# RFM69Pi_V5.net
KiCad netlist of a schematic drawn in EAGLE
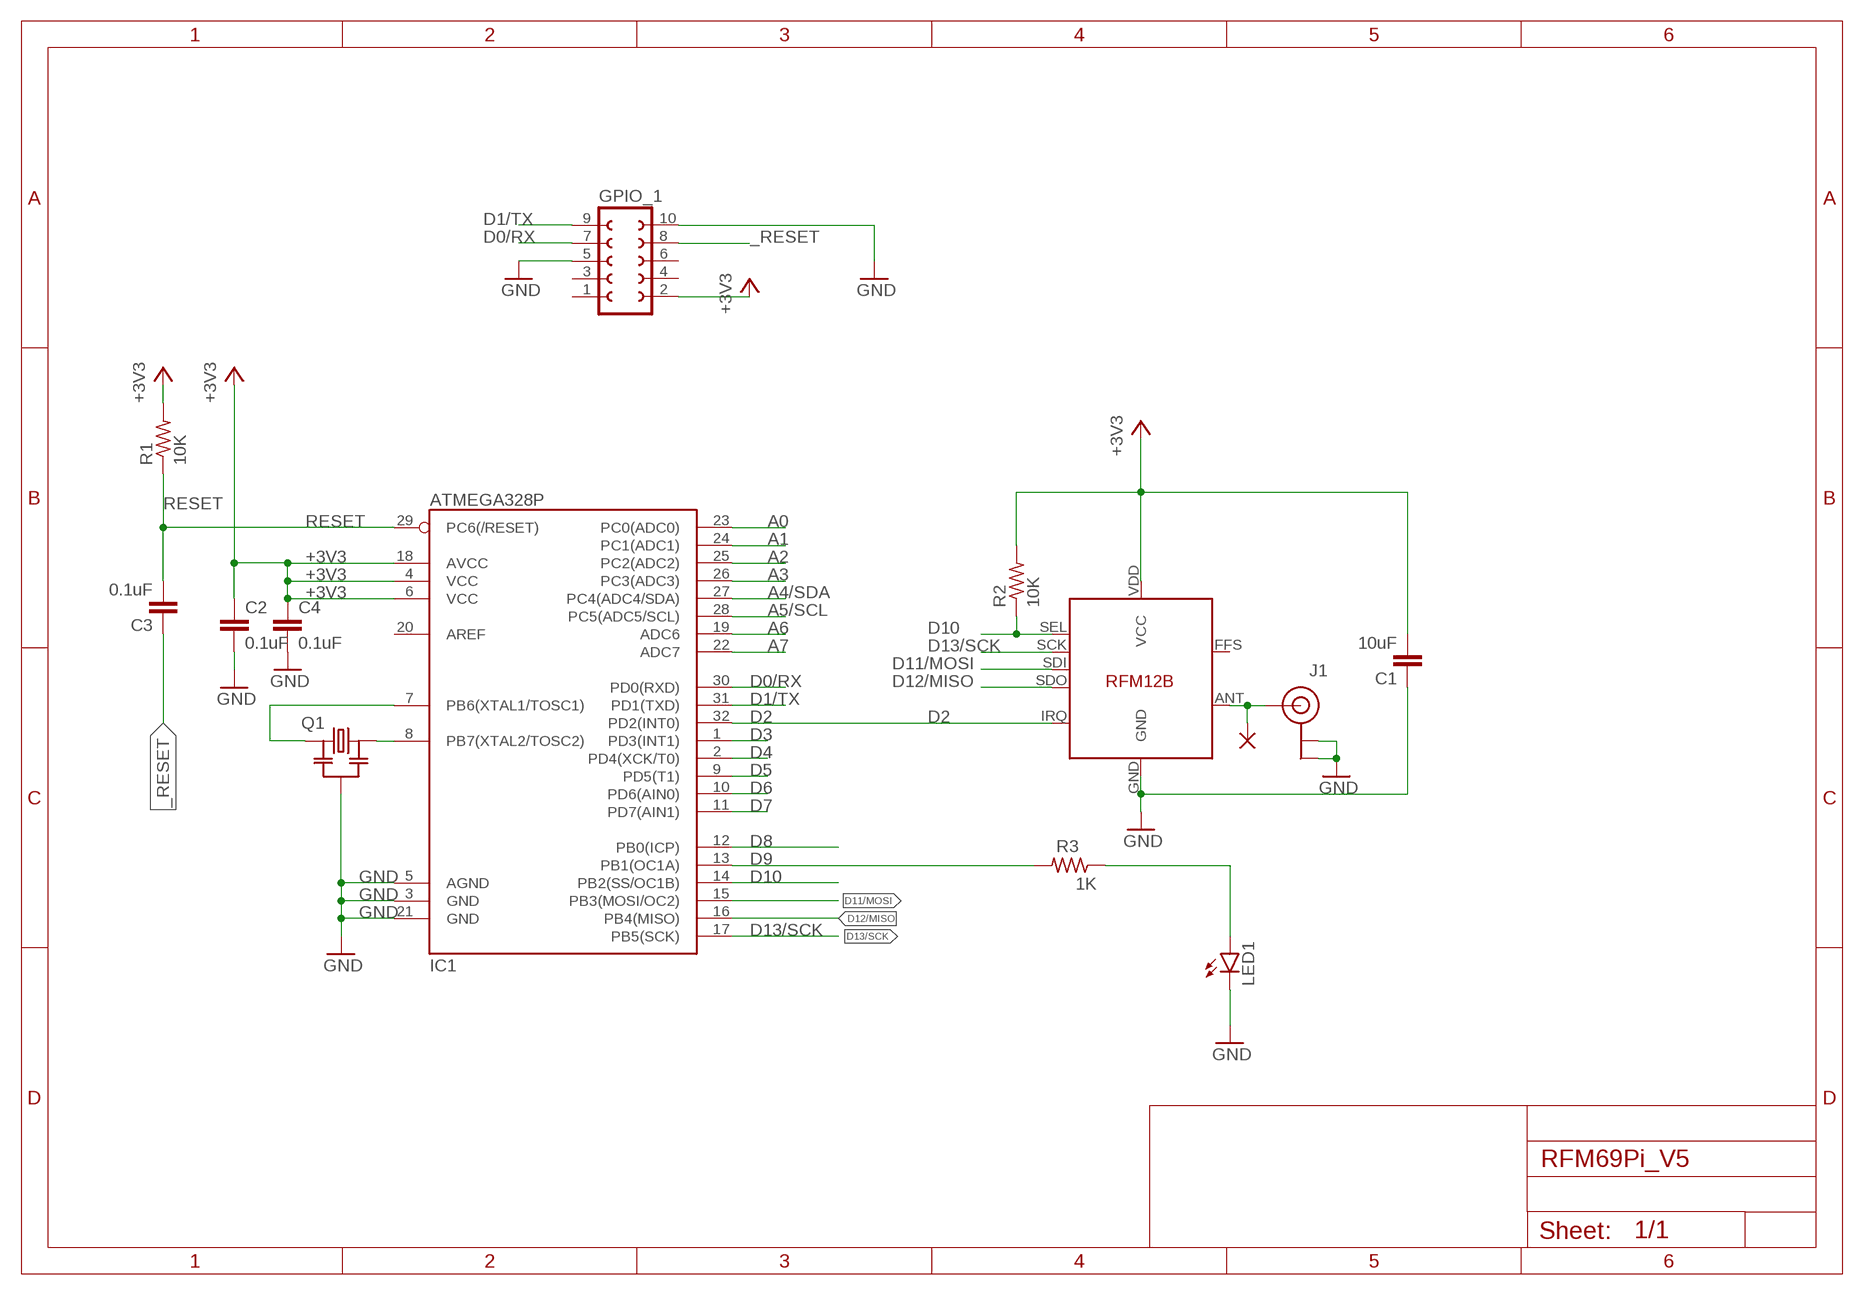
[diagram p0: schematic, sheet 1]

(export (version "E")
  (design (tool "Eeschema 10.0.6"))
  (components
    (comp (ref "C1")
      (value "10uF")
      (footprint "eagle-import:C0603")
      (libsource (lib "eagle-import") (part "C-EUC0603"))
    )
    (comp (ref "C2")
      (value "0.1uF")
      (footprint "eagle-import:C0603")
      (libsource (lib "eagle-import") (part "C-EUC0603"))
    )
    (comp (ref "C3")
      (value "0.1uF")
      (footprint "eagle-import:C0603")
      (libsource (lib "eagle-import") (part "C-EUC0603"))
    )
    (comp (ref "C4")
      (value "0.1uF")
      (footprint "eagle-import:C0603")
      (libsource (lib "eagle-import") (part "resistor_348_C-EUC0603"))
    )
    (comp (ref "GPIO_1")
      (value "CON-LSTA_FE05-2")
      (footprint "eagle-import:CON-LSTA_FE05-2")
      (libsource (lib "eagle-import") (part "CON-LSTA_FE05-2"))
    )
    (comp (ref "IC1")
      (value "ATMEGA328P")
      (footprint "eagle-import:TQFP32-08")
      (libsource (lib "eagle-import") (part "ATMEGA168"))
    )
    (comp (ref "J1")
      (value "U.FL")
      (footprint "eagle-import:U.FL")
      (libsource (lib "eagle-import") (part "U.FL"))
    )
    (comp (ref "LED1")
      (value "LEDSML0603")
      (footprint "eagle-import:SML0603")
      (libsource (lib "eagle-import") (part "LEDSML0603"))
    )
    (comp (ref "PAD2")
      (value "1,6/0,8")
      (footprint "eagle-import:1,6_0,8")
      (libsource (lib "eagle-import") (part "1,6/0,8"))
    )
    (comp (ref "Q1")
      (value "RESONATOR-MURATACST_CE")
      (footprint "eagle-import:RESONATOR_MURATA2")
      (libsource (lib "eagle-import") (part "RESONATOR-MURATACST_CE"))
    )
    (comp (ref "R1")
      (value "10K")
      (footprint "eagle-import:R0603")
      (libsource (lib "eagle-import") (part "R-US_R0603"))
    )
    (comp (ref "R2")
      (value "10K")
      (footprint "eagle-import:R0603")
      (libsource (lib "eagle-import") (part "R-US_R0603"))
    )
    (comp (ref "R3")
      (value "1K")
      (footprint "eagle-import:R0603")
      (libsource (lib "eagle-import") (part "R-US_R0603"))
    )
    (comp (ref "RFM69CW")
      (value "RFM69CW")
      (footprint "eagle-import:RFM12B")
      (libsource (lib "eagle-import") (part "RFM12B"))
    )
  )
  (nets
    (net (code "1") (name "+3V3") (class "Default")
      (node (ref "C1") (pin "2") (pinfunction "2_2") (pintype "passive"))
      (node (ref "C2") (pin "1") (pinfunction "1_1") (pintype "passive"))
      (node (ref "C4") (pin "1") (pinfunction "1_1") (pintype "passive"))
      (node (ref "GPIO_1") (pin "2") (pinfunction "2_2") (pintype "passive"))
      (node (ref "IC1") (pin "18") (pinfunction "AVCC_18") (pintype "bidirectional"))
      (node (ref "IC1") (pin "4") (pinfunction "VCC_4") (pintype "bidirectional"))
      (node (ref "IC1") (pin "6") (pinfunction "VCC_6") (pintype "bidirectional"))
      (node (ref "R1") (pin "2") (pinfunction "2_2") (pintype "passive"))
      (node (ref "R2") (pin "2") (pinfunction "2_2") (pintype "passive"))
      (node (ref "RFM69CW") (pin "VDD") (pinfunction "VCC_VDD") (pintype "power_in"))
    )
    (net (code "2") (name "/A0") (class "Default")
      (node (ref "IC1") (pin "23") (pinfunction "PC0(ADC0)_23") (pintype "bidirectional"))
    )
    (net (code "3") (name "/A1") (class "Default")
      (node (ref "IC1") (pin "24") (pinfunction "PC1(ADC1)_24") (pintype "bidirectional"))
    )
    (net (code "4") (name "/A2") (class "Default")
      (node (ref "IC1") (pin "25") (pinfunction "PC2(ADC2)_25") (pintype "bidirectional"))
    )
    (net (code "5") (name "/A3") (class "Default")
      (node (ref "IC1") (pin "26") (pinfunction "PC3(ADC3)_26") (pintype "bidirectional"))
    )
    (net (code "6") (name "/A4{slash}SDA") (class "Default")
      (node (ref "IC1") (pin "27") (pinfunction "PC4(ADC4/SDA)_27") (pintype "bidirectional"))
    )
    (net (code "7") (name "/A5{slash}SCL") (class "Default")
      (node (ref "IC1") (pin "28") (pinfunction "PC5(ADC5/SCL)_28") (pintype "bidirectional"))
    )
    (net (code "8") (name "/A6") (class "Default")
      (node (ref "IC1") (pin "19") (pinfunction "ADC6_19") (pintype "bidirectional"))
    )
    (net (code "9") (name "/A7") (class "Default")
      (node (ref "IC1") (pin "22") (pinfunction "ADC7_22") (pintype "bidirectional"))
    )
    (net (code "10") (name "/D0{slash}RX") (class "Default")
      (node (ref "GPIO_1") (pin "7") (pinfunction "7_7") (pintype "passive"))
      (node (ref "IC1") (pin "30") (pinfunction "PD0(RXD)_30") (pintype "bidirectional"))
    )
    (net (code "11") (name "/D1{slash}TX") (class "Default")
      (node (ref "GPIO_1") (pin "9") (pinfunction "9_9") (pintype "passive"))
      (node (ref "IC1") (pin "31") (pinfunction "PD1(TXD)_31") (pintype "bidirectional"))
    )
    (net (code "12") (name "/D2") (class "Default")
      (node (ref "IC1") (pin "32") (pinfunction "PD2(INT0)_32") (pintype "bidirectional"))
      (node (ref "RFM69CW") (pin "IRQ") (pinfunction "IRQ_IRQ") (pintype "open_collector"))
    )
    (net (code "13") (name "/D3") (class "Default")
      (node (ref "IC1") (pin "1") (pinfunction "PD3(INT1)_1") (pintype "bidirectional"))
    )
    (net (code "14") (name "/D4") (class "Default")
      (node (ref "IC1") (pin "2") (pinfunction "PD4(XCK/T0)_2") (pintype "bidirectional"))
    )
    (net (code "15") (name "/D5") (class "Default")
      (node (ref "IC1") (pin "9") (pinfunction "PD5(T1)_9") (pintype "bidirectional"))
    )
    (net (code "16") (name "/D6") (class "Default")
      (node (ref "IC1") (pin "10") (pinfunction "PD6(AIN0)_10") (pintype "bidirectional"))
    )
    (net (code "17") (name "/D7") (class "Default")
      (node (ref "IC1") (pin "11") (pinfunction "PD7(AIN1)_11") (pintype "bidirectional"))
    )
    (net (code "18") (name "/D8") (class "Default")
      (node (ref "IC1") (pin "12") (pinfunction "PB0(ICP)_12") (pintype "bidirectional"))
    )
    (net (code "19") (name "/D9") (class "Default")
      (node (ref "IC1") (pin "13") (pinfunction "PB1(OC1A)_13") (pintype "bidirectional"))
      (node (ref "R3") (pin "2") (pinfunction "2_2") (pintype "passive"))
    )
    (net (code "20") (name "/D10") (class "Default")
      (node (ref "IC1") (pin "14") (pinfunction "PB2(SS/OC1B)_14") (pintype "bidirectional"))
      (node (ref "R2") (pin "1") (pinfunction "1_1") (pintype "passive"))
      (node (ref "RFM69CW") (pin "SEL") (pinfunction "SEL_SEL") (pintype "input"))
    )
    (net (code "21") (name "/RESET") (class "Default")
      (node (ref "C3") (pin "2") (pinfunction "2_2") (pintype "passive"))
      (node (ref "IC1") (pin "29") (pinfunction "PC6(/RESET)_29") (pintype "bidirectional"))
      (node (ref "R1") (pin "1") (pinfunction "1_1") (pintype "passive"))
    )
    (net (code "22") (name "D11{slash}MOSI") (class "Default")
      (node (ref "IC1") (pin "15") (pinfunction "PB3(MOSI/OC2)_15") (pintype "bidirectional"))
      (node (ref "RFM69CW") (pin "SDI") (pinfunction "SDI_SDI") (pintype "input"))
    )
    (net (code "23") (name "D12{slash}MISO") (class "Default")
      (node (ref "IC1") (pin "16") (pinfunction "PB4(MISO)_16") (pintype "bidirectional"))
      (node (ref "RFM69CW") (pin "SDO") (pinfunction "SDO_SDO") (pintype "output"))
    )
    (net (code "24") (name "D13{slash}SCK") (class "Default")
      (node (ref "IC1") (pin "17") (pinfunction "PB5(SCK)_17") (pintype "bidirectional"))
      (node (ref "RFM69CW") (pin "SCK") (pinfunction "SCK_SCK") (pintype "input"))
    )
    (net (code "25") (name "GND") (class "Default")
      (node (ref "C1") (pin "1") (pinfunction "1_1") (pintype "passive"))
      (node (ref "C2") (pin "2") (pinfunction "2_2") (pintype "passive"))
      (node (ref "C4") (pin "2") (pinfunction "2_2") (pintype "passive"))
      (node (ref "GPIO_1") (pin "10") (pinfunction "10_10") (pintype "passive"))
      (node (ref "GPIO_1") (pin "5") (pinfunction "5_5") (pintype "passive"))
      (node (ref "IC1") (pin "21") (pinfunction "GND_21") (pintype "bidirectional"))
      (node (ref "IC1") (pin "3") (pinfunction "GND_3") (pintype "bidirectional"))
      (node (ref "IC1") (pin "5") (pinfunction "AGND_5") (pintype "bidirectional"))
      (node (ref "J1") (pin "1") (pinfunction "GND_1") (pintype "bidirectional"))
      (node (ref "J1") (pin "2") (pinfunction "GND_2") (pintype "bidirectional"))
      (node (ref "LED1") (pin "C") (pinfunction "C_C") (pintype "passive"))
      (node (ref "Q1") (pin "2") (pinfunction "2_2") (pintype "passive"))
      (node (ref "RFM69CW") (pin "GND") (pinfunction "GND_GND") (pintype "power_in"))
    )
    (net (code "26") (name "Net-(IC1-PB6(XTAL1{slash}TOSC1))") (class "Default")
      (node (ref "IC1") (pin "7") (pinfunction "PB6(XTAL1/TOSC1)_7") (pintype "bidirectional"))
      (node (ref "Q1") (pin "1") (pinfunction "1_1") (pintype "passive"))
    )
    (net (code "27") (name "Net-(IC1-PB7(XTAL2{slash}TOSC2))") (class "Default")
      (node (ref "IC1") (pin "8") (pinfunction "PB7(XTAL2/TOSC2)_8") (pintype "bidirectional"))
      (node (ref "Q1") (pin "3") (pinfunction "3_3") (pintype "passive"))
    )
    (net (code "28") (name "Net-(J1-SIGNAL)") (class "Default")
      (node (ref "J1") (pin "FEED") (pinfunction "SIGNAL_FEED") (pintype "bidirectional"))
      (node (ref "PAD2") (pin "1") (pinfunction "P_1") (pintype "passive"))
      (node (ref "RFM69CW") (pin "ANT") (pinfunction "ANT_ANT") (pintype "passive"))
    )
    (net (code "29") (name "Net-(LED1-PadA)") (class "Default")
      (node (ref "LED1") (pin "A") (pinfunction "A_A") (pintype "passive"))
      (node (ref "R3") (pin "1") (pinfunction "1_1") (pintype "passive"))
    )
    (net (code "30") (name "_RESET") (class "Default")
      (node (ref "C3") (pin "1") (pinfunction "1_1") (pintype "passive"))
      (node (ref "GPIO_1") (pin "8") (pinfunction "8_8") (pintype "passive"))
    )
    (net (code "31") (name "unconnected-(GPIO_1-Pad1)") (class "Default")
      (node (ref "GPIO_1") (pin "1") (pinfunction "1_1") (pintype "passive"))
    )
    (net (code "32") (name "unconnected-(GPIO_1-Pad3)") (class "Default")
      (node (ref "GPIO_1") (pin "3") (pinfunction "3_3") (pintype "passive"))
    )
    (net (code "33") (name "unconnected-(GPIO_1-Pad4)") (class "Default")
      (node (ref "GPIO_1") (pin "4") (pinfunction "4_4") (pintype "passive"))
    )
    (net (code "34") (name "unconnected-(GPIO_1-Pad6)") (class "Default")
      (node (ref "GPIO_1") (pin "6") (pinfunction "6_6") (pintype "passive"))
    )
    (net (code "35") (name "unconnected-(IC1-AREF-Pad20)") (class "Default")
      (node (ref "IC1") (pin "20") (pinfunction "AREF_20") (pintype "bidirectional"))
    )
    (net (code "36") (name "unconnected-(RFM69CW-PadFFS)") (class "Default")
      (node (ref "RFM69CW") (pin "FFS") (pinfunction "FFS_FFS") (pintype "bidirectional"))
    )
  )
)
